# ioShield-A.net
KiCad netlist of a schematic drawn in EAGLE
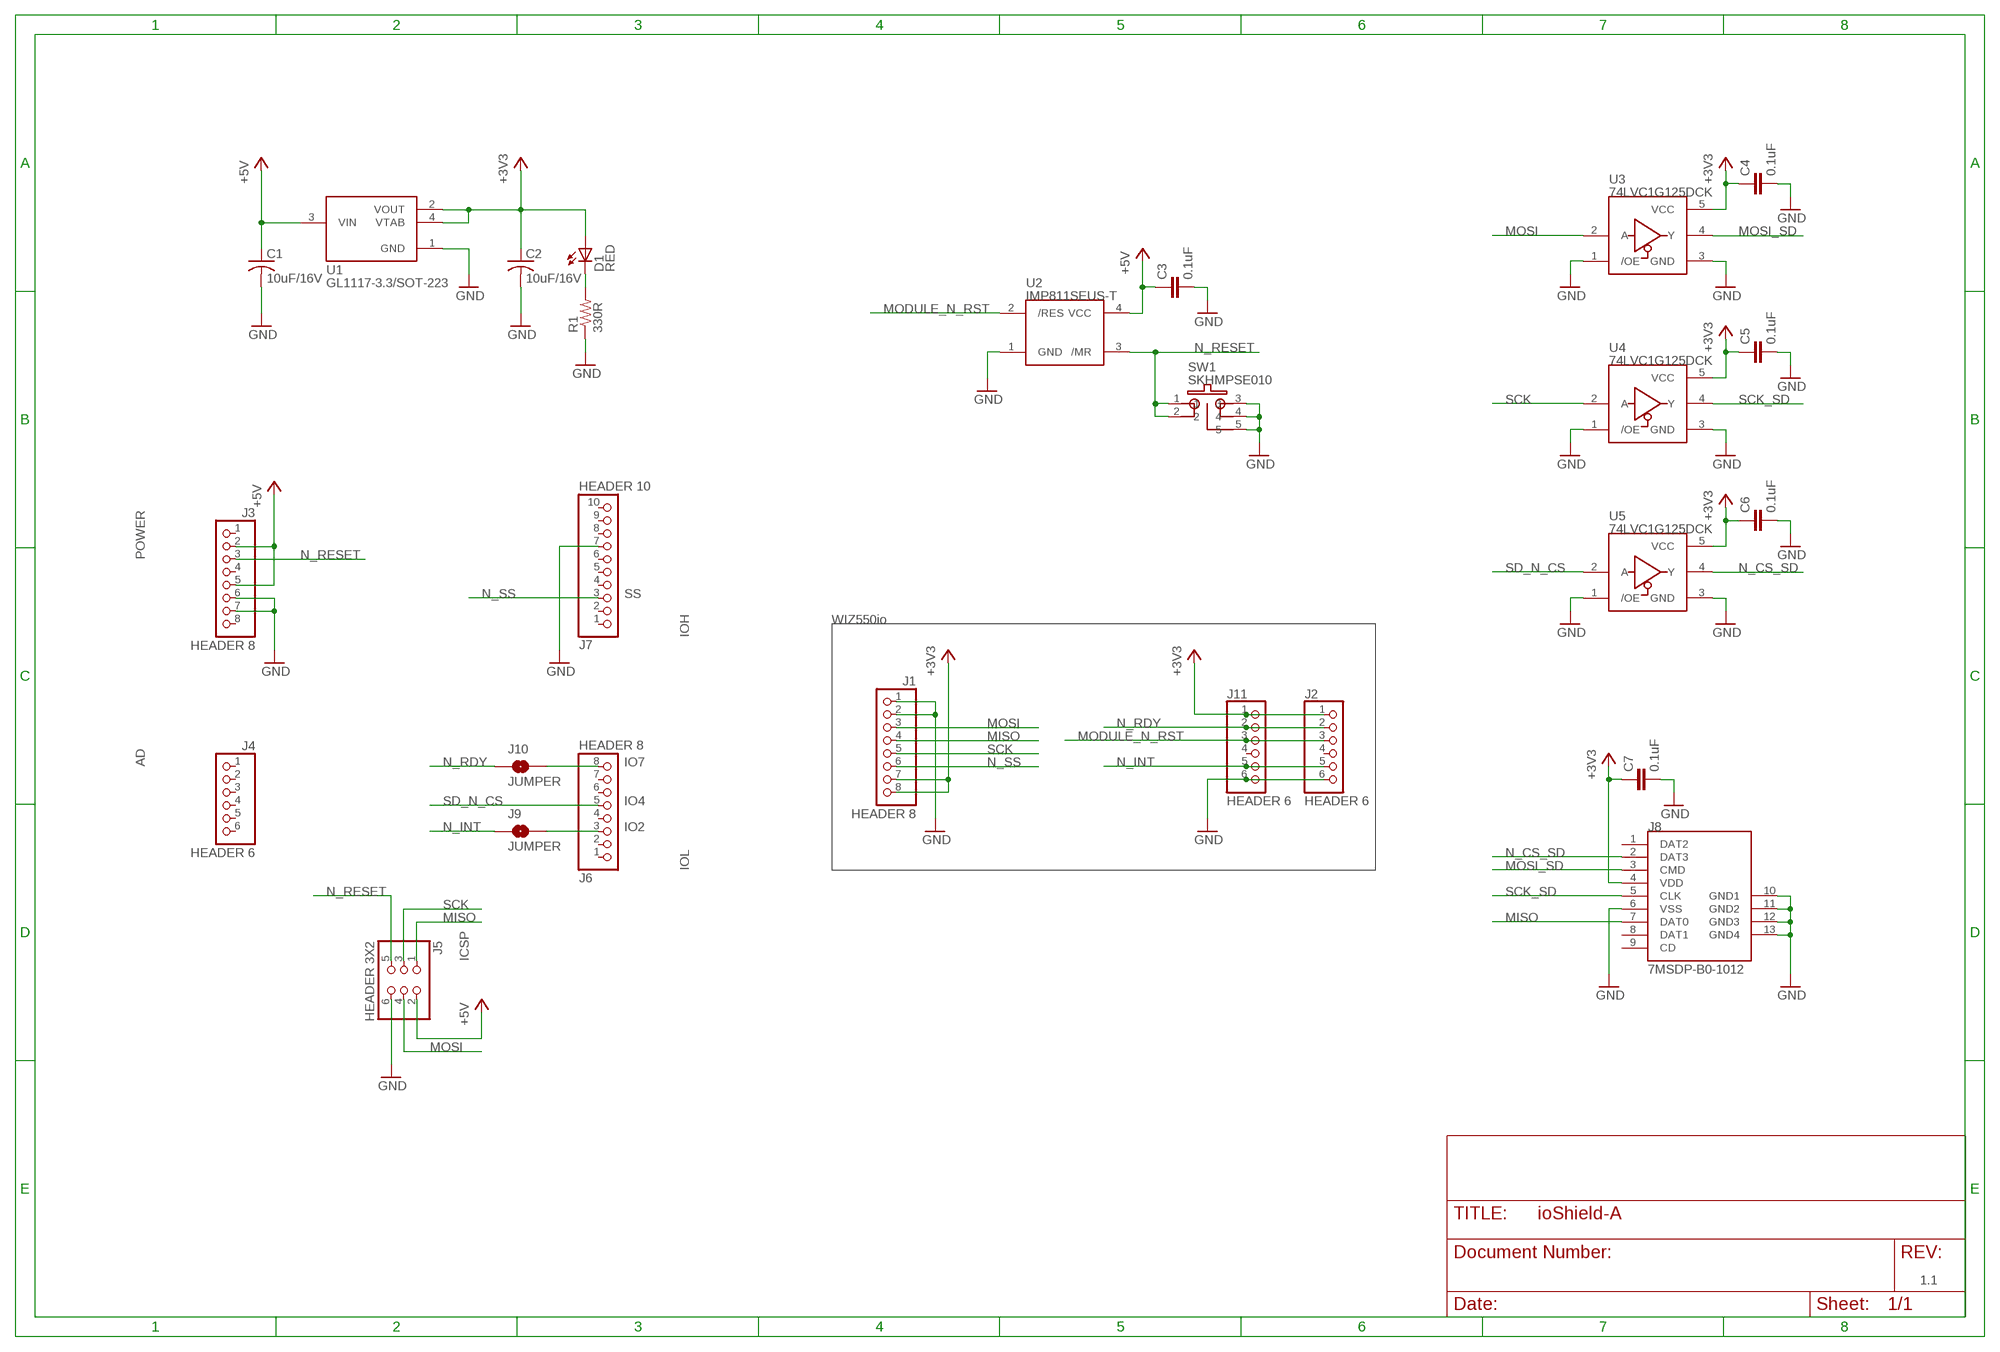
[diagram p0: schematic, sheet 1]

(export (version "E")
  (design (tool "Eeschema 10.0.6"))
  (components
    (comp (ref "C1")
      (value "10uF/16V")
      (footprint "eagle-import:CT-A(3216)")
      (libsource (lib "eagle-import") (part "CT-A(3216)"))
    )
    (comp (ref "C2")
      (value "10uF/16V")
      (footprint "eagle-import:CT-A(3216)")
      (libsource (lib "eagle-import") (part "CT-A(3216)"))
    )
    (comp (ref "C3")
      (value "0.1uF")
      (footprint "eagle-import:C1608")
      (libsource (lib "eagle-import") (part "C1608"))
    )
    (comp (ref "C4")
      (value "0.1uF")
      (footprint "eagle-import:C1608")
      (libsource (lib "eagle-import") (part "C1608"))
    )
    (comp (ref "C5")
      (value "0.1uF")
      (footprint "eagle-import:C1608")
      (libsource (lib "eagle-import") (part "C1608"))
    )
    (comp (ref "C6")
      (value "0.1uF")
      (footprint "eagle-import:C1608")
      (libsource (lib "eagle-import") (part "C1608"))
    )
    (comp (ref "C7")
      (value "0.1uF")
      (footprint "eagle-import:C1608")
      (libsource (lib "eagle-import") (part "C1608"))
    )
    (comp (ref "D1")
      (value "RED")
      (footprint "eagle-import:CHIP-LED1608")
      (libsource (lib "eagle-import") (part "LED1608"))
    )
    (comp (ref "J1")
      (value "HEADER 8")
      (footprint "eagle-import:HEADER1X8")
      (libsource (lib "eagle-import") (part "HEADER8"))
    )
    (comp (ref "J2")
      (value "HEADER 6")
      (footprint "eagle-import:HEADER1X6")
      (libsource (lib "eagle-import") (part "HEADER6"))
    )
    (comp (ref "J3")
      (value "HEADER 8")
      (footprint "eagle-import:HEADER1X8")
      (libsource (lib "eagle-import") (part "HEADER8"))
    )
    (comp (ref "J4")
      (value "HEADER 6")
      (footprint "eagle-import:HEADER1X6")
      (libsource (lib "eagle-import") (part "HEADER6"))
    )
    (comp (ref "J5")
      (value "HEADER 3X2")
      (footprint "eagle-import:HEADER3X2")
      (libsource (lib "eagle-import") (part "HEADER3X2"))
    )
    (comp (ref "J6")
      (value "HEADER 8")
      (footprint "eagle-import:HEADER1X8")
      (libsource (lib "eagle-import") (part "HEADER8"))
    )
    (comp (ref "J7")
      (value "HEADER 10")
      (footprint "eagle-import:HEADER1X10")
      (libsource (lib "eagle-import") (part "HEADER10"))
    )
    (comp (ref "J8")
      (value "7MSDP-B0-1012")
      (footprint "eagle-import:MICROSD_HC")
      (libsource (lib "eagle-import") (part "7MSDP-B0-1012"))
    )
    (comp (ref "J9")
      (value "JUMPER")
      (footprint "eagle-import:SJ")
      (libsource (lib "eagle-import") (part "SJ"))
    )
    (comp (ref "J10")
      (value "JUMPER")
      (footprint "eagle-import:SJ")
      (libsource (lib "eagle-import") (part "SJ"))
    )
    (comp (ref "J11")
      (value "HEADER 6")
      (footprint "eagle-import:HEADER1X6")
      (libsource (lib "eagle-import") (part "HEADER6"))
    )
    (comp (ref "R1")
      (value "330R")
      (footprint "eagle-import:R1608")
      (libsource (lib "eagle-import") (part "R1608"))
    )
    (comp (ref "SW1")
      (value "SKHMPSE010")
      (footprint "eagle-import:TACT_6.2X6.5")
      (libsource (lib "eagle-import") (part "TACT_6.2X6.5"))
    )
    (comp (ref "U1")
      (value "GL1117-3.3/SOT-223")
      (footprint "eagle-import:SOT223_HC")
      (libsource (lib "eagle-import") (part "GL1117-3.3/SOT-223"))
    )
    (comp (ref "U2")
      (value "IMP811SEUS-T")
      (footprint "eagle-import:SOT-143")
      (libsource (lib "eagle-import") (part "IMP811SEUS-T"))
    )
    (comp (ref "U3")
      (value "74LVC1G125DCK")
      (footprint "eagle-import:SC70-5(DCK)")
      (libsource (lib "eagle-import") (part "SN74LVC1G125"))
    )
    (comp (ref "U4")
      (value "74LVC1G125DCK")
      (footprint "eagle-import:SC70-5(DCK)")
      (libsource (lib "eagle-import") (part "SN74LVC1G125"))
    )
    (comp (ref "U5")
      (value "74LVC1G125DCK")
      (footprint "eagle-import:SC70-5(DCK)")
      (libsource (lib "eagle-import") (part "SN74LVC1G125"))
    )
  )
  (nets
    (net (code "1") (name "+3V3") (class "Default")
      (node (ref "C2") (pin "+") (pinfunction "1_+") (pintype "passive"))
      (node (ref "C4") (pin "1") (pinfunction "1_1") (pintype "passive"))
      (node (ref "C5") (pin "1") (pinfunction "1_1") (pintype "passive"))
      (node (ref "C6") (pin "1") (pinfunction "1_1") (pintype "passive"))
      (node (ref "C7") (pin "1") (pinfunction "1_1") (pintype "passive"))
      (node (ref "D1") (pin "A") (pinfunction "A_A") (pintype "passive"))
      (node (ref "J1") (pin "7") (pinfunction "7_7") (pintype "passive"))
      (node (ref "J1") (pin "8") (pinfunction "8_8") (pintype "passive"))
      (node (ref "J11") (pin "1") (pinfunction "1_1") (pintype "passive"))
      (node (ref "J2") (pin "1") (pinfunction "1_1") (pintype "passive"))
      (node (ref "J8") (pin "4") (pinfunction "VDD_4") (pintype "passive"))
      (node (ref "U1") (pin "2") (pinfunction "VOUT_2") (pintype "passive"))
      (node (ref "U1") (pin "4") (pinfunction "VTAB_4") (pintype "passive"))
      (node (ref "U3") (pin "5") (pinfunction "VCC_5") (pintype "passive"))
      (node (ref "U4") (pin "5") (pinfunction "VCC_5") (pintype "passive"))
      (node (ref "U5") (pin "5") (pinfunction "VCC_5") (pintype "passive"))
    )
    (net (code "2") (name "+5V") (class "Default")
      (node (ref "C1") (pin "+") (pinfunction "1_+") (pintype "passive"))
      (node (ref "C3") (pin "1") (pinfunction "1_1") (pintype "passive"))
      (node (ref "J3") (pin "2") (pinfunction "2_2") (pintype "passive"))
      (node (ref "J3") (pin "5") (pinfunction "5_5") (pintype "passive"))
      (node (ref "J5") (pin "2") (pinfunction "2_2") (pintype "passive"))
      (node (ref "U1") (pin "3") (pinfunction "VIN_3") (pintype "passive"))
      (node (ref "U2") (pin "4") (pinfunction "VCC_4") (pintype "passive"))
    )
    (net (code "3") (name "/MISO") (class "Default")
      (node (ref "J1") (pin "4") (pinfunction "4_4") (pintype "passive"))
      (node (ref "J5") (pin "1") (pinfunction "1_1") (pintype "passive"))
      (node (ref "J8") (pin "7") (pinfunction "DAT0_7") (pintype "passive"))
    )
    (net (code "4") (name "/MODULE_N_RST") (class "Default")
      (node (ref "J11") (pin "3") (pinfunction "3_3") (pintype "passive"))
      (node (ref "J2") (pin "3") (pinfunction "3_3") (pintype "passive"))
      (node (ref "U2") (pin "2") (pinfunction "/RES_2") (pintype "passive"))
    )
    (net (code "5") (name "/MOSI") (class "Default")
      (node (ref "J1") (pin "3") (pinfunction "3_3") (pintype "passive"))
      (node (ref "J5") (pin "4") (pinfunction "4_4") (pintype "passive"))
      (node (ref "U3") (pin "2") (pinfunction "A_2") (pintype "passive"))
    )
    (net (code "6") (name "/MOSI_SD") (class "Default")
      (node (ref "J8") (pin "3") (pinfunction "CMD_3") (pintype "passive"))
      (node (ref "U3") (pin "4") (pinfunction "Y_4") (pintype "passive"))
    )
    (net (code "7") (name "/N_CS_SD") (class "Default")
      (node (ref "J8") (pin "2") (pinfunction "DAT3_2") (pintype "passive"))
      (node (ref "U5") (pin "4") (pinfunction "Y_4") (pintype "passive"))
    )
    (net (code "8") (name "/N_INT") (class "Default")
      (node (ref "J11") (pin "5") (pinfunction "5_5") (pintype "passive"))
      (node (ref "J2") (pin "5") (pinfunction "5_5") (pintype "passive"))
      (node (ref "J9") (pin "1") (pinfunction "1_1") (pintype "passive"))
    )
    (net (code "9") (name "/N_RDY") (class "Default")
      (node (ref "J10") (pin "1") (pinfunction "1_1") (pintype "passive"))
      (node (ref "J11") (pin "2") (pinfunction "2_2") (pintype "passive"))
      (node (ref "J2") (pin "2") (pinfunction "2_2") (pintype "passive"))
    )
    (net (code "10") (name "/N_RESET") (class "Default")
      (node (ref "J3") (pin "3") (pinfunction "3_3") (pintype "passive"))
      (node (ref "J5") (pin "5") (pinfunction "5_5") (pintype "passive"))
      (node (ref "SW1") (pin "1") (pinfunction "1_1") (pintype "passive"))
      (node (ref "SW1") (pin "2") (pinfunction "2_2") (pintype "passive"))
      (node (ref "U2") (pin "3") (pinfunction "/MR_3") (pintype "passive"))
    )
    (net (code "11") (name "/N_SS") (class "Default")
      (node (ref "J1") (pin "6") (pinfunction "6_6") (pintype "passive"))
      (node (ref "J7") (pin "3") (pinfunction "3_3") (pintype "passive"))
    )
    (net (code "12") (name "/SCK") (class "Default")
      (node (ref "J1") (pin "5") (pinfunction "5_5") (pintype "passive"))
      (node (ref "J5") (pin "3") (pinfunction "3_3") (pintype "passive"))
      (node (ref "U4") (pin "2") (pinfunction "A_2") (pintype "passive"))
    )
    (net (code "13") (name "/SCK_SD") (class "Default")
      (node (ref "J8") (pin "5") (pinfunction "CLK_5") (pintype "passive"))
      (node (ref "U4") (pin "4") (pinfunction "Y_4") (pintype "passive"))
    )
    (net (code "14") (name "/SD_N_CS") (class "Default")
      (node (ref "J6") (pin "5") (pinfunction "5_5") (pintype "passive"))
      (node (ref "U5") (pin "2") (pinfunction "A_2") (pintype "passive"))
    )
    (net (code "15") (name "GND") (class "Default")
      (node (ref "C1") (pin "-") (pinfunction "2_-") (pintype "passive"))
      (node (ref "C2") (pin "-") (pinfunction "2_-") (pintype "passive"))
      (node (ref "C3") (pin "2") (pinfunction "2_2") (pintype "passive"))
      (node (ref "C4") (pin "2") (pinfunction "2_2") (pintype "passive"))
      (node (ref "C5") (pin "2") (pinfunction "2_2") (pintype "passive"))
      (node (ref "C6") (pin "2") (pinfunction "2_2") (pintype "passive"))
      (node (ref "C7") (pin "2") (pinfunction "2_2") (pintype "passive"))
      (node (ref "J1") (pin "1") (pinfunction "1_1") (pintype "passive"))
      (node (ref "J1") (pin "2") (pinfunction "2_2") (pintype "passive"))
      (node (ref "J11") (pin "6") (pinfunction "6_6") (pintype "passive"))
      (node (ref "J2") (pin "6") (pinfunction "6_6") (pintype "passive"))
      (node (ref "J3") (pin "6") (pinfunction "6_6") (pintype "passive"))
      (node (ref "J3") (pin "7") (pinfunction "7_7") (pintype "passive"))
      (node (ref "J5") (pin "6") (pinfunction "6_6") (pintype "passive"))
      (node (ref "J7") (pin "7") (pinfunction "7_7") (pintype "passive"))
      (node (ref "J8") (pin "10") (pinfunction "GND1_10") (pintype "passive"))
      (node (ref "J8") (pin "11") (pinfunction "GND2_11") (pintype "passive"))
      (node (ref "J8") (pin "12") (pinfunction "GND3_12") (pintype "passive"))
      (node (ref "J8") (pin "13") (pinfunction "GND4_13") (pintype "passive"))
      (node (ref "J8") (pin "6") (pinfunction "VSS_6") (pintype "passive"))
      (node (ref "R1") (pin "1") (pinfunction "1_1") (pintype "passive"))
      (node (ref "SW1") (pin "3") (pinfunction "3_3") (pintype "passive"))
      (node (ref "SW1") (pin "4") (pinfunction "4_4") (pintype "passive"))
      (node (ref "SW1") (pin "5") (pinfunction "5_5") (pintype "passive"))
      (node (ref "U1") (pin "1") (pinfunction "GND_1") (pintype "passive"))
      (node (ref "U2") (pin "1") (pinfunction "GND_1") (pintype "passive"))
      (node (ref "U3") (pin "1") (pinfunction "/OE_1") (pintype "passive"))
      (node (ref "U3") (pin "3") (pinfunction "GND_3") (pintype "passive"))
      (node (ref "U4") (pin "1") (pinfunction "/OE_1") (pintype "passive"))
      (node (ref "U4") (pin "3") (pinfunction "GND_3") (pintype "passive"))
      (node (ref "U5") (pin "1") (pinfunction "/OE_1") (pintype "passive"))
      (node (ref "U5") (pin "3") (pinfunction "GND_3") (pintype "passive"))
    )
    (net (code "16") (name "Net-(D1-PadC)") (class "Default")
      (node (ref "D1") (pin "C") (pinfunction "C_C") (pintype "passive"))
      (node (ref "R1") (pin "2") (pinfunction "2_2") (pintype "passive"))
    )
    (net (code "17") (name "Net-(J6-Pad3)") (class "Default")
      (node (ref "J6") (pin "3") (pinfunction "3_3") (pintype "passive"))
      (node (ref "J9") (pin "2") (pinfunction "2_2") (pintype "passive"))
    )
    (net (code "18") (name "Net-(J10-Pad2)") (class "Default")
      (node (ref "J10") (pin "2") (pinfunction "2_2") (pintype "passive"))
      (node (ref "J6") (pin "8") (pinfunction "8_8") (pintype "passive"))
    )
    (net (code "19") (name "unconnected-(J2-Pad4)") (class "Default")
      (node (ref "J2") (pin "4") (pinfunction "4_4") (pintype "passive"))
    )
    (net (code "20") (name "unconnected-(J3-Pad1)") (class "Default")
      (node (ref "J3") (pin "1") (pinfunction "1_1") (pintype "passive"))
    )
    (net (code "21") (name "unconnected-(J3-Pad4)") (class "Default")
      (node (ref "J3") (pin "4") (pinfunction "4_4") (pintype "passive"))
    )
    (net (code "22") (name "unconnected-(J3-Pad8)") (class "Default")
      (node (ref "J3") (pin "8") (pinfunction "8_8") (pintype "passive"))
    )
    (net (code "23") (name "unconnected-(J4-Pad1)") (class "Default")
      (node (ref "J4") (pin "1") (pinfunction "1_1") (pintype "passive"))
    )
    (net (code "24") (name "unconnected-(J4-Pad2)") (class "Default")
      (node (ref "J4") (pin "2") (pinfunction "2_2") (pintype "passive"))
    )
    (net (code "25") (name "unconnected-(J4-Pad3)") (class "Default")
      (node (ref "J4") (pin "3") (pinfunction "3_3") (pintype "passive"))
    )
    (net (code "26") (name "unconnected-(J4-Pad4)") (class "Default")
      (node (ref "J4") (pin "4") (pinfunction "4_4") (pintype "passive"))
    )
    (net (code "27") (name "unconnected-(J4-Pad5)") (class "Default")
      (node (ref "J4") (pin "5") (pinfunction "5_5") (pintype "passive"))
    )
    (net (code "28") (name "unconnected-(J4-Pad6)") (class "Default")
      (node (ref "J4") (pin "6") (pinfunction "6_6") (pintype "passive"))
    )
    (net (code "29") (name "unconnected-(J6-Pad1)") (class "Default")
      (node (ref "J6") (pin "1") (pinfunction "1_1") (pintype "passive"))
    )
    (net (code "30") (name "unconnected-(J6-Pad2)") (class "Default")
      (node (ref "J6") (pin "2") (pinfunction "2_2") (pintype "passive"))
    )
    (net (code "31") (name "unconnected-(J6-Pad4)") (class "Default")
      (node (ref "J6") (pin "4") (pinfunction "4_4") (pintype "passive"))
    )
    (net (code "32") (name "unconnected-(J6-Pad6)") (class "Default")
      (node (ref "J6") (pin "6") (pinfunction "6_6") (pintype "passive"))
    )
    (net (code "33") (name "unconnected-(J6-Pad7)") (class "Default")
      (node (ref "J6") (pin "7") (pinfunction "7_7") (pintype "passive"))
    )
    (net (code "34") (name "unconnected-(J7-Pad1)") (class "Default")
      (node (ref "J7") (pin "1") (pinfunction "1_1") (pintype "passive"))
    )
    (net (code "35") (name "unconnected-(J7-Pad2)") (class "Default")
      (node (ref "J7") (pin "2") (pinfunction "2_2") (pintype "passive"))
    )
    (net (code "36") (name "unconnected-(J7-Pad4)") (class "Default")
      (node (ref "J7") (pin "4") (pinfunction "4_4") (pintype "passive"))
    )
    (net (code "37") (name "unconnected-(J7-Pad5)") (class "Default")
      (node (ref "J7") (pin "5") (pinfunction "5_5") (pintype "passive"))
    )
    (net (code "38") (name "unconnected-(J7-Pad6)") (class "Default")
      (node (ref "J7") (pin "6") (pinfunction "6_6") (pintype "passive"))
    )
    (net (code "39") (name "unconnected-(J7-Pad8)") (class "Default")
      (node (ref "J7") (pin "8") (pinfunction "8_8") (pintype "passive"))
    )
    (net (code "40") (name "unconnected-(J7-Pad9)") (class "Default")
      (node (ref "J7") (pin "9") (pinfunction "9_9") (pintype "passive"))
    )
    (net (code "41") (name "unconnected-(J7-Pad10)") (class "Default")
      (node (ref "J7") (pin "10") (pinfunction "10_10") (pintype "passive"))
    )
    (net (code "42") (name "unconnected-(J8-CD-Pad9)") (class "Default")
      (node (ref "J8") (pin "9") (pinfunction "CD_9") (pintype "passive"))
    )
    (net (code "43") (name "unconnected-(J8-DAT1-Pad8)") (class "Default")
      (node (ref "J8") (pin "8") (pinfunction "DAT1_8") (pintype "passive"))
    )
    (net (code "44") (name "unconnected-(J8-DAT2-Pad1)") (class "Default")
      (node (ref "J8") (pin "1") (pinfunction "DAT2_1") (pintype "passive"))
    )
    (net (code "45") (name "unconnected-(J11-Pad4)") (class "Default")
      (node (ref "J11") (pin "4") (pinfunction "4_4") (pintype "passive"))
    )
  )
)
